# Schematics.net
KiCad netlist of a schematic drawn in Altium Designer
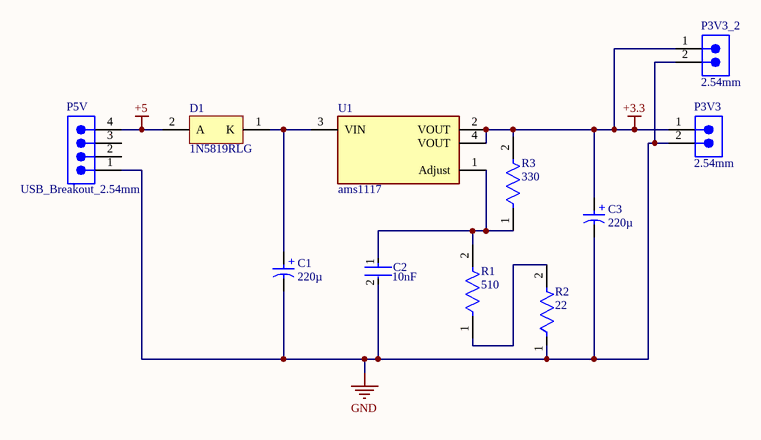
[diagram p0: Schematics.SchDoc]

(export (version "E")
  (design (tool "Eeschema 10.0.6"))
  (components
    (comp (ref "C1")
      (value "220µ")
      (footprint "WCAP-ATUL_D10H25")
      (description "860040775010 Alum. Electrolytic Cap 220µF 63V 10mm Radial WCAP-ATUL; Lifetime 7000h +105°C")
      (fields (field (name "TOLERANCE") "20%"))
      (libsource (lib "Altium Content Vault") (part "Capacitor_Polarized"))
    )
    (comp (ref "C2")
      (value "10nF")
      (footprint "FP-C0805C-DN-MFG")
      (description "CAP CER 10000PF 200V X7R 0805")
      (fields
        (field (name "OCTOPART") "https://octopart.com/c0805c103k2ractu-kemet-9138347")
        (field (name "MANUFACTURER PART NUMBER") "C0805C103K2RACTU")
      )
      (libsource (lib "Altium Content Vault") (part "b4654b650e69147ec39a6b967a45e02"))
    )
    (comp (ref "C3")
      (value "220µ")
      (footprint "WCAP-ATUL_D10H25")
      (description "860040775010 Alum. Electrolytic Cap 220µF 63V 10mm Radial WCAP-ATUL; Lifetime 7000h +105°C")
      (fields (field (name "TOLERANCE") "20%"))
      (libsource (lib "Altium Content Vault") (part "Capacitor_Polarized"))
    )
    (comp (ref "D1")
      (value "1N5819RLG")
      (footprint "ONSC-AXIAL_LEAD-2-59-10_P")
      (description "Rectifier, 2-Pin Axial_Lead, Pb-Free, Tape and Reel")
      (fields (field (name "MANUFACTURER") "On Semiconductor"))
      (libsource (lib "Altium Content Vault") (part "ONSC-D-K1A2-2_A"))
    )
    (comp (ref "P3V3")
      (value "2.54mm")
      (footprint "61300211121")
      (libsource (lib "Altium Content Vault") (part "Header_Male_1R_02P"))
    )
    (comp (ref "P3V3_2")
      (value "2.54mm")
      (footprint "61300211121")
      (libsource (lib "Altium Content Vault") (part "Header_Male_1R_02P"))
    )
    (comp (ref "P5V")
      (value "USB_Breakout_2.54mm")
      (footprint "61300411121")
      (libsource (lib "Altium Content Vault") (part "Header_Male_1R_04P"))
    )
    (comp (ref "R1")
      (value "510")
      (footprint "FP-MRS25-MFG")
      (description "MRS25000C1000FRP00 Resistor,  ± 1%, 600 mW, Axial Leaded, Metal Film (Thin Film), Professional")
      (fields (field (name "TOLERANCE") "1%"))
      (libsource (lib "Altium Content Vault") (part "1029c3af85768c4190bb7ad29bc67b5"))
    )
    (comp (ref "R2")
      (value "22")
      (footprint "FP-MRS25-MFG")
      (description "MRS25000C1000FRP00 Resistor,  ± 1%, 600 mW, Axial Leaded, Metal Film (Thin Film), Professional")
      (fields (field (name "TOLERANCE") "1%"))
      (libsource (lib "Altium Content Vault") (part "1029c3af85768c4190bb7ad29bc67b5"))
    )
    (comp (ref "R3")
      (value "330")
      (footprint "FP-MRS25-MFG")
      (description "MRS25000C1000FRP00 Resistor,  ± 1%, 600 mW, Axial Leaded, Metal Film (Thin Film), Professional")
      (fields (field (name "TOLERANCE") "1%"))
      (libsource (lib "Altium Content Vault") (part "1029c3af85768c4190bb7ad29bc67b5"))
    )
    (comp (ref "U1")
      (value "ams1117")
      (footprint "FP-ams1117-IPC_C")
      (description "1A LOW DROPOUT VOLTAGE REGULATOR")
      (libsource (lib "Altium Content Vault") (part "59ad430b93a2c51b3e6ee7c3b069677"))
    )
  )
  (nets
    (net (code "1") (name "+3.3") (class "Default")
      (node (ref "C3") (pin "1") (pinfunction "P_1") (pintype "passive"))
      (node (ref "P3V3") (pin "1") (pinfunction "1_1") (pintype "passive"))
      (node (ref "P3V3_2") (pin "1") (pinfunction "1_1") (pintype "passive"))
      (node (ref "R3") (pin "2") (pinfunction "2_2") (pintype "passive"))
      (node (ref "U1") (pin "2") (pinfunction "VOUT_2") (pintype "passive"))
      (node (ref "U1") (pin "4") (pinfunction "VOUT_4") (pintype "passive"))
    )
    (net (code "2") (name "+5") (class "Default")
      (node (ref "D1") (pin "2") (pinfunction "A_2") (pintype "passive"))
      (node (ref "P5V") (pin "4") (pinfunction "4_4") (pintype "passive"))
    )
    (net (code "3") (name "GND") (class "Default")
      (node (ref "C1") (pin "2") (pinfunction "N_2") (pintype "passive"))
      (node (ref "C2") (pin "2") (pinfunction "2_2") (pintype "passive"))
      (node (ref "C3") (pin "2") (pinfunction "N_2") (pintype "passive"))
      (node (ref "P3V3") (pin "2") (pinfunction "2_2") (pintype "passive"))
      (node (ref "P3V3_2") (pin "2") (pinfunction "2_2") (pintype "passive"))
      (node (ref "P5V") (pin "1") (pinfunction "1_1") (pintype "passive"))
      (node (ref "R2") (pin "1") (pinfunction "1_1") (pintype "passive"))
    )
    (net (code "4") (name "Net-(C1-P)") (class "Default")
      (node (ref "C1") (pin "1") (pinfunction "P_1") (pintype "passive"))
      (node (ref "D1") (pin "1") (pinfunction "K_1") (pintype "passive"))
      (node (ref "U1") (pin "3") (pinfunction "VIN_3") (pintype "power_in"))
    )
    (net (code "5") (name "Net-(R1-Pad1)") (class "Default")
      (node (ref "R1") (pin "1") (pinfunction "1_1") (pintype "passive"))
      (node (ref "R2") (pin "2") (pinfunction "2_2") (pintype "passive"))
    )
    (net (code "6") (name "Net-(U1-Adjust)") (class "Default")
      (node (ref "C2") (pin "1") (pinfunction "1_1") (pintype "passive"))
      (node (ref "R1") (pin "2") (pinfunction "2_2") (pintype "passive"))
      (node (ref "R3") (pin "1") (pinfunction "1_1") (pintype "passive"))
      (node (ref "U1") (pin "1") (pinfunction "Adjust_1") (pintype "passive"))
    )
    (net (code "7") (name "unconnected-(P5V-Pad2)") (class "Default")
      (node (ref "P5V") (pin "2") (pinfunction "2_2") (pintype "passive"))
    )
    (net (code "8") (name "unconnected-(P5V-Pad3)") (class "Default")
      (node (ref "P5V") (pin "3") (pinfunction "3_3") (pintype "passive"))
    )
  )
)
